# part.net
KiCad netlist of a schematic drawn in Altium Designer
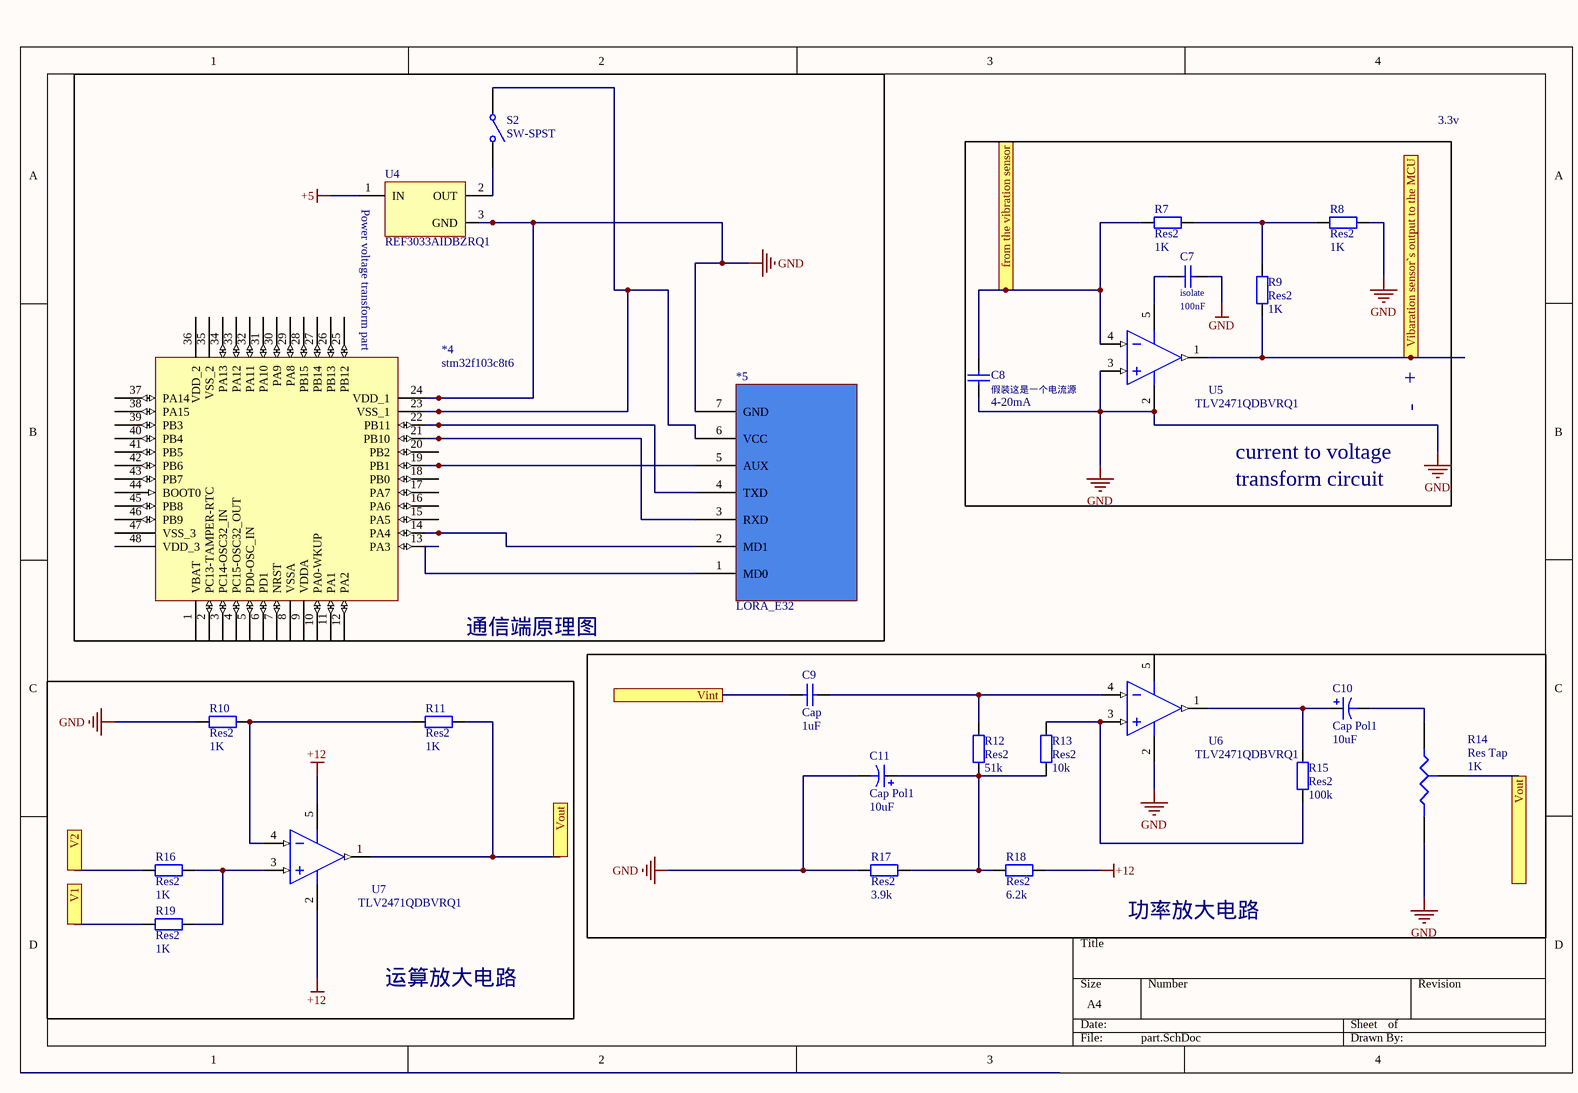
[diagram p0: part.SchDoc]

(export (version "E")
  (design (tool "Eeschema 10.0.6"))
  (components
    (comp (ref "*4") (value "stm32f103c8t6") (libsource (lib "stm32f103c8t6") (part "stm32f103c8t6")))
    (comp (ref "*5")
      (value "LORA_E32")
      (footprint "LORA_AS62-T20")
      (description "EBYTE_USE_SEMTCH_CORE")
      (libsource (lib "lora") (part "LORA_E32"))
    )
    (comp (ref "C7")
      (value "isolate")
      (footprint "RAD-0.3")
      (description "Capacitor")
      (fields (field (name "ALTIUM_VALUE") "100nF") (field (name "PUBLISHER") "Altium Limited"))
      (libsource (lib "Miscellaneous Devices") (part "Cap"))
    )
    (comp (ref "C8")
      (value "假装这是一个电流源")
      (footprint "RAD-0.3")
      (description "Capacitor")
      (fields (field (name "ALTIUM_VALUE") "4-20mA") (field (name "PUBLISHER") "Altium Limited"))
      (libsource (lib "Miscellaneous Devices") (part "Cap"))
    )
    (comp (ref "C9")
      (value "Cap")
      (footprint "RAD-0.3")
      (description "Capacitor")
      (fields (field (name "ALTIUM_VALUE") "1uF") (field (name "PUBLISHER") "Altium Limited"))
      (libsource (lib "Miscellaneous Devices") (part "Cap"))
    )
    (comp (ref "C10")
      (value "Cap Pol1")
      (footprint "RB7.6-15")
      (description "Polarized Capacitor (Radial)")
      (fields (field (name "ALTIUM_VALUE") "10uF") (field (name "PUBLISHER") "Altium Limited"))
      (libsource (lib "Miscellaneous Devices") (part "Cap Pol1"))
    )
    (comp (ref "C11")
      (value "Cap Pol1")
      (footprint "RB7.6-15")
      (description "Polarized Capacitor (Radial)")
      (fields (field (name "ALTIUM_VALUE") "10uF") (field (name "PUBLISHER") "Altium Limited"))
      (libsource (lib "Miscellaneous Devices") (part "Cap Pol1"))
    )
    (comp (ref "R7")
      (value "Res2")
      (footprint "AXIAL-0.4")
      (description "Resistor")
      (fields (field (name "ALTIUM_VALUE") "1K") (field (name "PUBLISHER") "Altium Limited"))
      (libsource (lib "") (part "Res2_1"))
    )
    (comp (ref "R8")
      (value "Res2")
      (footprint "AXIAL-0.4")
      (description "Resistor")
      (fields (field (name "ALTIUM_VALUE") "1K") (field (name "PUBLISHER") "Altium Limited"))
      (libsource (lib "") (part "Res2_2"))
    )
    (comp (ref "R9")
      (value "Res2")
      (footprint "AXIAL-0.4")
      (description "Resistor")
      (fields (field (name "ALTIUM_VALUE") "1K") (field (name "PUBLISHER") "Altium Limited"))
      (libsource (lib "Miscellaneous Devices") (part "Res2"))
    )
    (comp (ref "R10")
      (value "Res2")
      (footprint "AXIAL-0.4")
      (description "Resistor")
      (fields (field (name "ALTIUM_VALUE") "1K") (field (name "PUBLISHER") "Altium Limited"))
      (libsource (lib "") (part "Res2_2"))
    )
    (comp (ref "R11")
      (value "Res2")
      (footprint "AXIAL-0.4")
      (description "Resistor")
      (fields (field (name "ALTIUM_VALUE") "1K") (field (name "PUBLISHER") "Altium Limited"))
      (libsource (lib "") (part "Res2_2"))
    )
    (comp (ref "R12")
      (value "Res2")
      (footprint "AXIAL-0.4")
      (description "Resistor")
      (fields (field (name "ALTIUM_VALUE") "51k") (field (name "PUBLISHER") "Altium Limited"))
      (libsource (lib "Miscellaneous Devices") (part "Res2"))
    )
    (comp (ref "R13")
      (value "Res2")
      (footprint "AXIAL-0.4")
      (description "Resistor")
      (fields (field (name "ALTIUM_VALUE") "10k") (field (name "PUBLISHER") "Altium Limited"))
      (libsource (lib "Miscellaneous Devices") (part "Res2"))
    )
    (comp (ref "R14")
      (value "Res Tap")
      (footprint "VR3")
      (description "Tapped Resistor")
      (fields (field (name "ALTIUM_VALUE") "1K") (field (name "PUBLISHER") "Altium Limited"))
      (libsource (lib "Miscellaneous Devices") (part "Res Tap"))
    )
    (comp (ref "R15")
      (value "Res2")
      (footprint "AXIAL-0.4")
      (description "Resistor")
      (fields (field (name "ALTIUM_VALUE") "100k") (field (name "PUBLISHER") "Altium Limited"))
      (libsource (lib "Miscellaneous Devices") (part "Res2"))
    )
    (comp (ref "R16")
      (value "Res2")
      (footprint "AXIAL-0.4")
      (description "Resistor")
      (fields (field (name "ALTIUM_VALUE") "1K") (field (name "PUBLISHER") "Altium Limited"))
      (libsource (lib "") (part "Res2_2"))
    )
    (comp (ref "R17")
      (value "Res2")
      (footprint "AXIAL-0.4")
      (description "Resistor")
      (fields (field (name "ALTIUM_VALUE") "3.9k") (field (name "PUBLISHER") "Altium Limited"))
      (libsource (lib "") (part "Res2_1"))
    )
    (comp (ref "R18")
      (value "Res2")
      (footprint "AXIAL-0.4")
      (description "Resistor")
      (fields (field (name "ALTIUM_VALUE") "6.2k") (field (name "PUBLISHER") "Altium Limited"))
      (libsource (lib "") (part "Res2_1"))
    )
    (comp (ref "R19")
      (value "Res2")
      (footprint "AXIAL-0.4")
      (description "Resistor")
      (fields (field (name "ALTIUM_VALUE") "1K") (field (name "PUBLISHER") "Altium Limited"))
      (libsource (lib "") (part "Res2_2"))
    )
    (comp (ref "S2")
      (value "SW-SPST")
      (footprint "SPST-2")
      (description "Single-Pole, Single-Throw Switch")
      (fields (field (name "PUBLISHER") "Altium Limited"))
      (libsource (lib "Miscellaneous Devices") (part "SW-SPST"))
    )
    (comp (ref "U4")
      (value "REF3033AIDBZRQ1")
      (footprint "TI-DBZ3_N")
      (fields (field (name "MANUFACTURER") "Texas Instruments"))
      (libsource (lib "TI Power Management Series Voltage Reference") (part "REF3033AIDBZRQ1"))
    )
    (comp (ref "U5")
      (value "TLV2471QDBVRQ1")
      (footprint "TI-DBV5_N")
      (fields (field (name "MANUFACTURER") "Texas Instruments"))
      (libsource (lib "TI Amplifiers and Linear Operational Amplifier Precision Amplifier Part Two") (part "TLV2471QDBVRQ1"))
    )
    (comp (ref "U6")
      (value "TLV2471QDBVRQ1")
      (footprint "TI-DBV5_N")
      (fields (field (name "MANUFACTURER") "Texas Instruments"))
      (libsource (lib "TI Amplifiers and Linear Operational Amplifier Precision Amplifier Part Two") (part "TLV2471QDBVRQ1"))
    )
    (comp (ref "U7")
      (value "TLV2471QDBVRQ1")
      (footprint "TI-DBV5_N")
      (fields (field (name "MANUFACTURER") "Texas Instruments"))
      (libsource (lib "TI Amplifiers and Linear Operational Amplifier Precision Amplifier Part Two") (part "TLV2471QDBVRQ1"))
    )
  )
  (nets
    (net (code "1") (name "+5") (class "Default")
      (node (ref "U4") (pin "1") (pinfunction "IN_1") (pintype "power_in"))
    )
    (net (code "2") (name "+12") (class "Default")
      (node (ref "R18") (pin "1") (pinfunction "1_1") (pintype "passive"))
      (node (ref "U7") (pin "2") (pinfunction "GND_2") (pintype "power_in"))
      (node (ref "U7") (pin "5") (pinfunction "VDD_5") (pintype "power_in"))
    )
    (net (code "3") (name "/V1") (class "Default")
      (node (ref "R19") (pin "1") (pinfunction "1_1") (pintype "passive"))
    )
    (net (code "4") (name "/V2") (class "Default")
      (node (ref "R16") (pin "1") (pinfunction "1_1") (pintype "passive"))
    )
    (net (code "5") (name "/Vibaration sensor`s output to the MCU") (class "Default")
      (node (ref "R9") (pin "1") (pinfunction "1_1") (pintype "passive"))
      (node (ref "U5") (pin "1") (pinfunction "OUT_1") (pintype "output"))
    )
    (net (code "6") (name "/Vint") (class "Default")
      (node (ref "C9") (pin "1") (pinfunction "1_1") (pintype "passive"))
    )
    (net (code "7") (name "/Vout") (class "Default")
      (node (ref "R11") (pin "2") (pinfunction "2_2") (pintype "passive"))
      (node (ref "R14") (pin "3") (pinfunction "TAP_3") (pintype "passive"))
      (node (ref "U7") (pin "1") (pinfunction "OUT_1") (pintype "output"))
    )
    (net (code "8") (name "/from the vibration sensor") (class "Default")
      (node (ref "C8") (pin "2") (pinfunction "2_2") (pintype "passive"))
      (node (ref "R7") (pin "2") (pinfunction "2_2") (pintype "passive"))
      (node (ref "U5") (pin "4") (pinfunction "IN-_4") (pintype "input"))
    )
    (net (code "9") (name "GND") (class "Default")
      (node (ref "*4") (pin "24") (pinfunction "VDD_1_24") (pintype "power_in"))
      (node (ref "*5") (pin "7") (pinfunction "GND_7") (pintype "passive"))
      (node (ref "C11") (pin "2") (pinfunction "2_2") (pintype "passive"))
      (node (ref "C7") (pin "1") (pinfunction "1_1") (pintype "passive"))
      (node (ref "C8") (pin "1") (pinfunction "1_1") (pintype "passive"))
      (node (ref "R10") (pin "1") (pinfunction "1_1") (pintype "passive"))
      (node (ref "R14") (pin "2") (pinfunction "B_2") (pintype "passive"))
      (node (ref "R17") (pin "2") (pinfunction "2_2") (pintype "passive"))
      (node (ref "R8") (pin "2") (pinfunction "2_2") (pintype "passive"))
      (node (ref "U4") (pin "3") (pinfunction "GND_3") (pintype "power_in"))
      (node (ref "U5") (pin "2") (pinfunction "GND_2") (pintype "power_in"))
      (node (ref "U5") (pin "3") (pinfunction "IN+_3") (pintype "input"))
      (node (ref "U6") (pin "2") (pinfunction "GND_2") (pintype "power_in"))
    )
    (net (code "10") (name "Net-(*4-PA3)") (class "Default")
      (node (ref "*4") (pin "13") (pinfunction "PA3_13") (pintype "bidirectional"))
      (node (ref "*5") (pin "1") (pinfunction "MD0_1") (pintype "passive"))
    )
    (net (code "11") (name "Net-(*4-PA4)") (class "Default")
      (node (ref "*4") (pin "14") (pinfunction "PA4_14") (pintype "bidirectional"))
      (node (ref "*5") (pin "2") (pinfunction "MD1_2") (pintype "passive"))
    )
    (net (code "12") (name "Net-(*4-PB1)") (class "Default")
      (node (ref "*4") (pin "19") (pinfunction "PB1_19") (pintype "bidirectional"))
      (node (ref "*5") (pin "5") (pinfunction "AUX_5") (pintype "passive"))
    )
    (net (code "13") (name "Net-(*4-PB10)") (class "Default")
      (node (ref "*4") (pin "21") (pinfunction "PB10_21") (pintype "bidirectional"))
      (node (ref "*5") (pin "3") (pinfunction "RXD_3") (pintype "passive"))
    )
    (net (code "14") (name "Net-(*4-PB11)") (class "Default")
      (node (ref "*4") (pin "22") (pinfunction "PB11_22") (pintype "bidirectional"))
      (node (ref "*5") (pin "4") (pinfunction "TXD_4") (pintype "passive"))
    )
    (net (code "15") (name "Net-(*4-VSS_1)") (class "Default")
      (node (ref "*4") (pin "23") (pinfunction "VSS_1_23") (pintype "power_in"))
      (node (ref "*5") (pin "6") (pinfunction "VCC_6") (pintype "power_in"))
      (node (ref "S2") (pin "1") (pinfunction "COMMON_1") (pintype "passive"))
    )
    (net (code "16") (name "Net-(C11-Pad1)") (class "Default")
      (node (ref "C11") (pin "1") (pinfunction "1_1") (pintype "passive"))
      (node (ref "R12") (pin "1") (pinfunction "1_1") (pintype "passive"))
      (node (ref "R13") (pin "1") (pinfunction "1_1") (pintype "passive"))
      (node (ref "R17") (pin "1") (pinfunction "1_1") (pintype "passive"))
      (node (ref "R18") (pin "2") (pinfunction "2_2") (pintype "passive"))
    )
    (net (code "17") (name "Net-(R7-Pad1)") (class "Default")
      (node (ref "R7") (pin "1") (pinfunction "1_1") (pintype "passive"))
      (node (ref "R8") (pin "1") (pinfunction "1_1") (pintype "passive"))
      (node (ref "R9") (pin "2") (pinfunction "2_2") (pintype "passive"))
    )
    (net (code "18") (name "Net-(R14-A)") (class "Default")
      (node (ref "C10") (pin "2") (pinfunction "2_2") (pintype "passive"))
      (node (ref "R14") (pin "1") (pinfunction "A_1") (pintype "passive"))
    )
    (net (code "19") (name "Net-(S2-NO)") (class "Default")
      (node (ref "S2") (pin "2") (pinfunction "NO_2") (pintype "passive"))
      (node (ref "U4") (pin "2") (pinfunction "OUT_2") (pintype "power_in"))
    )
    (net (code "20") (name "Net-(U5-VDD)") (class "Default")
      (node (ref "C7") (pin "2") (pinfunction "2_2") (pintype "passive"))
      (node (ref "U5") (pin "5") (pinfunction "VDD_5") (pintype "power_in"))
    )
    (net (code "21") (name "Net-(U6-IN+)") (class "Default")
      (node (ref "R13") (pin "2") (pinfunction "2_2") (pintype "passive"))
      (node (ref "R15") (pin "1") (pinfunction "1_1") (pintype "passive"))
      (node (ref "U6") (pin "3") (pinfunction "IN+_3") (pintype "input"))
    )
    (net (code "22") (name "Net-(U6-IN-)") (class "Default")
      (node (ref "C9") (pin "2") (pinfunction "2_2") (pintype "passive"))
      (node (ref "R12") (pin "2") (pinfunction "2_2") (pintype "passive"))
      (node (ref "U6") (pin "4") (pinfunction "IN-_4") (pintype "input"))
    )
    (net (code "23") (name "Net-(U6-OUT)") (class "Default")
      (node (ref "C10") (pin "1") (pinfunction "1_1") (pintype "passive"))
      (node (ref "R15") (pin "2") (pinfunction "2_2") (pintype "passive"))
      (node (ref "U6") (pin "1") (pinfunction "OUT_1") (pintype "output"))
    )
    (net (code "24") (name "Net-(U7-IN+)") (class "Default")
      (node (ref "R16") (pin "2") (pinfunction "2_2") (pintype "passive"))
      (node (ref "R19") (pin "2") (pinfunction "2_2") (pintype "passive"))
      (node (ref "U7") (pin "3") (pinfunction "IN+_3") (pintype "input"))
    )
    (net (code "25") (name "Net-(U7-IN-)") (class "Default")
      (node (ref "R10") (pin "2") (pinfunction "2_2") (pintype "passive"))
      (node (ref "R11") (pin "1") (pinfunction "1_1") (pintype "passive"))
      (node (ref "U7") (pin "4") (pinfunction "IN-_4") (pintype "input"))
    )
    (net (code "26") (name "unconnected-(*4-BOOT0-Pad44)") (class "Default")
      (node (ref "*4") (pin "44") (pinfunction "BOOT0_44") (pintype "input"))
    )
    (net (code "27") (name "unconnected-(*4-NRST-Pad7)") (class "Default")
      (node (ref "*4") (pin "7") (pinfunction "NRST_7") (pintype "bidirectional"))
    )
    (net (code "28") (name "unconnected-(*4-PA0-WKUP-Pad10)") (class "Default")
      (node (ref "*4") (pin "10") (pinfunction "PA0-WKUP_10") (pintype "bidirectional"))
    )
    (net (code "29") (name "unconnected-(*4-PA1-Pad11)") (class "Default")
      (node (ref "*4") (pin "11") (pinfunction "PA1_11") (pintype "bidirectional"))
    )
    (net (code "30") (name "unconnected-(*4-PA2-Pad12)") (class "Default")
      (node (ref "*4") (pin "12") (pinfunction "PA2_12") (pintype "bidirectional"))
    )
    (net (code "31") (name "unconnected-(*4-PA5-Pad15)") (class "Default")
      (node (ref "*4") (pin "15") (pinfunction "PA5_15") (pintype "bidirectional"))
    )
    (net (code "32") (name "unconnected-(*4-PA6-Pad16)") (class "Default")
      (node (ref "*4") (pin "16") (pinfunction "PA6_16") (pintype "bidirectional"))
    )
    (net (code "33") (name "unconnected-(*4-PA7-Pad17)") (class "Default")
      (node (ref "*4") (pin "17") (pinfunction "PA7_17") (pintype "bidirectional"))
    )
    (net (code "34") (name "unconnected-(*4-PA8-Pad29)") (class "Default")
      (node (ref "*4") (pin "29") (pinfunction "PA8_29") (pintype "bidirectional"))
    )
    (net (code "35") (name "unconnected-(*4-PA9-Pad30)") (class "Default")
      (node (ref "*4") (pin "30") (pinfunction "PA9_30") (pintype "bidirectional"))
    )
    (net (code "36") (name "unconnected-(*4-PA10-Pad31)") (class "Default")
      (node (ref "*4") (pin "31") (pinfunction "PA10_31") (pintype "bidirectional"))
    )
    (net (code "37") (name "unconnected-(*4-PA11-Pad32)") (class "Default")
      (node (ref "*4") (pin "32") (pinfunction "PA11_32") (pintype "bidirectional"))
    )
    (net (code "38") (name "unconnected-(*4-PA12-Pad33)") (class "Default")
      (node (ref "*4") (pin "33") (pinfunction "PA12_33") (pintype "bidirectional"))
    )
    (net (code "39") (name "unconnected-(*4-PA13-Pad34)") (class "Default")
      (node (ref "*4") (pin "34") (pinfunction "PA13_34") (pintype "bidirectional"))
    )
    (net (code "40") (name "unconnected-(*4-PA14-Pad37)") (class "Default")
      (node (ref "*4") (pin "37") (pinfunction "PA14_37") (pintype "bidirectional"))
    )
    (net (code "41") (name "unconnected-(*4-PA15-Pad38)") (class "Default")
      (node (ref "*4") (pin "38") (pinfunction "PA15_38") (pintype "bidirectional"))
    )
    (net (code "42") (name "unconnected-(*4-PB0-Pad18)") (class "Default")
      (node (ref "*4") (pin "18") (pinfunction "PB0_18") (pintype "bidirectional"))
    )
    (net (code "43") (name "unconnected-(*4-PB2-Pad20)") (class "Default")
      (node (ref "*4") (pin "20") (pinfunction "PB2_20") (pintype "bidirectional"))
    )
    (net (code "44") (name "unconnected-(*4-PB3-Pad39)") (class "Default")
      (node (ref "*4") (pin "39") (pinfunction "PB3_39") (pintype "bidirectional"))
    )
    (net (code "45") (name "unconnected-(*4-PB4-Pad40)") (class "Default")
      (node (ref "*4") (pin "40") (pinfunction "PB4_40") (pintype "bidirectional"))
    )
    (net (code "46") (name "unconnected-(*4-PB5-Pad41)") (class "Default")
      (node (ref "*4") (pin "41") (pinfunction "PB5_41") (pintype "bidirectional"))
    )
    (net (code "47") (name "unconnected-(*4-PB6-Pad42)") (class "Default")
      (node (ref "*4") (pin "42") (pinfunction "PB6_42") (pintype "bidirectional"))
    )
    (net (code "48") (name "unconnected-(*4-PB7-Pad43)") (class "Default")
      (node (ref "*4") (pin "43") (pinfunction "PB7_43") (pintype "bidirectional"))
    )
    (net (code "49") (name "unconnected-(*4-PB8-Pad45)") (class "Default")
      (node (ref "*4") (pin "45") (pinfunction "PB8_45") (pintype "bidirectional"))
    )
    (net (code "50") (name "unconnected-(*4-PB9-Pad46)") (class "Default")
      (node (ref "*4") (pin "46") (pinfunction "PB9_46") (pintype "bidirectional"))
    )
    (net (code "51") (name "unconnected-(*4-PB12-Pad25)") (class "Default")
      (node (ref "*4") (pin "25") (pinfunction "PB12_25") (pintype "bidirectional"))
    )
    (net (code "52") (name "unconnected-(*4-PB13-Pad26)") (class "Default")
      (node (ref "*4") (pin "26") (pinfunction "PB13_26") (pintype "bidirectional"))
    )
    (net (code "53") (name "unconnected-(*4-PB14-Pad27)") (class "Default")
      (node (ref "*4") (pin "27") (pinfunction "PB14_27") (pintype "bidirectional"))
    )
    (net (code "54") (name "unconnected-(*4-PB15-Pad28)") (class "Default")
      (node (ref "*4") (pin "28") (pinfunction "PB15_28") (pintype "bidirectional"))
    )
    (net (code "55") (name "unconnected-(*4-PC13-TAMPER-RTC-Pad2)") (class "Default")
      (node (ref "*4") (pin "2") (pinfunction "PC13-TAMPER-RTC_2") (pintype "bidirectional"))
    )
    (net (code "56") (name "unconnected-(*4-PC14-OSC32_IN-Pad3)") (class "Default")
      (node (ref "*4") (pin "3") (pinfunction "PC14-OSC32_IN_3") (pintype "bidirectional"))
    )
    (net (code "57") (name "unconnected-(*4-PC15-OSC32_OUT-Pad4)") (class "Default")
      (node (ref "*4") (pin "4") (pinfunction "PC15-OSC32_OUT_4") (pintype "bidirectional"))
    )
    (net (code "58") (name "unconnected-(*4-PD0-OSC_IN-Pad5)") (class "Default")
      (node (ref "*4") (pin "5") (pinfunction "PD0-OSC_IN_5") (pintype "bidirectional"))
    )
    (net (code "59") (name "unconnected-(*4-PD1-Pad6)") (class "Default")
      (node (ref "*4") (pin "6") (pinfunction "PD1_6") (pintype "bidirectional"))
    )
    (net (code "60") (name "unconnected-(*4-VBAT-Pad1)") (class "Default")
      (node (ref "*4") (pin "1") (pinfunction "VBAT_1") (pintype "power_in"))
    )
    (net (code "61") (name "unconnected-(*4-VDDA-Pad9)") (class "Default")
      (node (ref "*4") (pin "9") (pinfunction "VDDA_9") (pintype "power_in"))
    )
    (net (code "62") (name "unconnected-(*4-VDD_2-Pad36)") (class "Default")
      (node (ref "*4") (pin "36") (pinfunction "VDD_2_36") (pintype "power_in"))
    )
    (net (code "63") (name "unconnected-(*4-VDD_3-Pad48)") (class "Default")
      (node (ref "*4") (pin "48") (pinfunction "VDD_3_48") (pintype "power_in"))
    )
    (net (code "64") (name "unconnected-(*4-VSSA-Pad8)") (class "Default")
      (node (ref "*4") (pin "8") (pinfunction "VSSA_8") (pintype "power_in"))
    )
    (net (code "65") (name "unconnected-(*4-VSS_2-Pad35)") (class "Default")
      (node (ref "*4") (pin "35") (pinfunction "VSS_2_35") (pintype "power_in"))
    )
    (net (code "66") (name "unconnected-(*4-VSS_3-Pad47)") (class "Default")
      (node (ref "*4") (pin "47") (pinfunction "VSS_3_47") (pintype "power_in"))
    )
    (net (code "67") (name "unconnected-(U6-VDD-Pad5)") (class "Default")
      (node (ref "U6") (pin "5") (pinfunction "VDD_5") (pintype "power_in"))
    )
  )
)
